# 4-Connector.net
KiCad netlist of a schematic drawn in Altium Designer
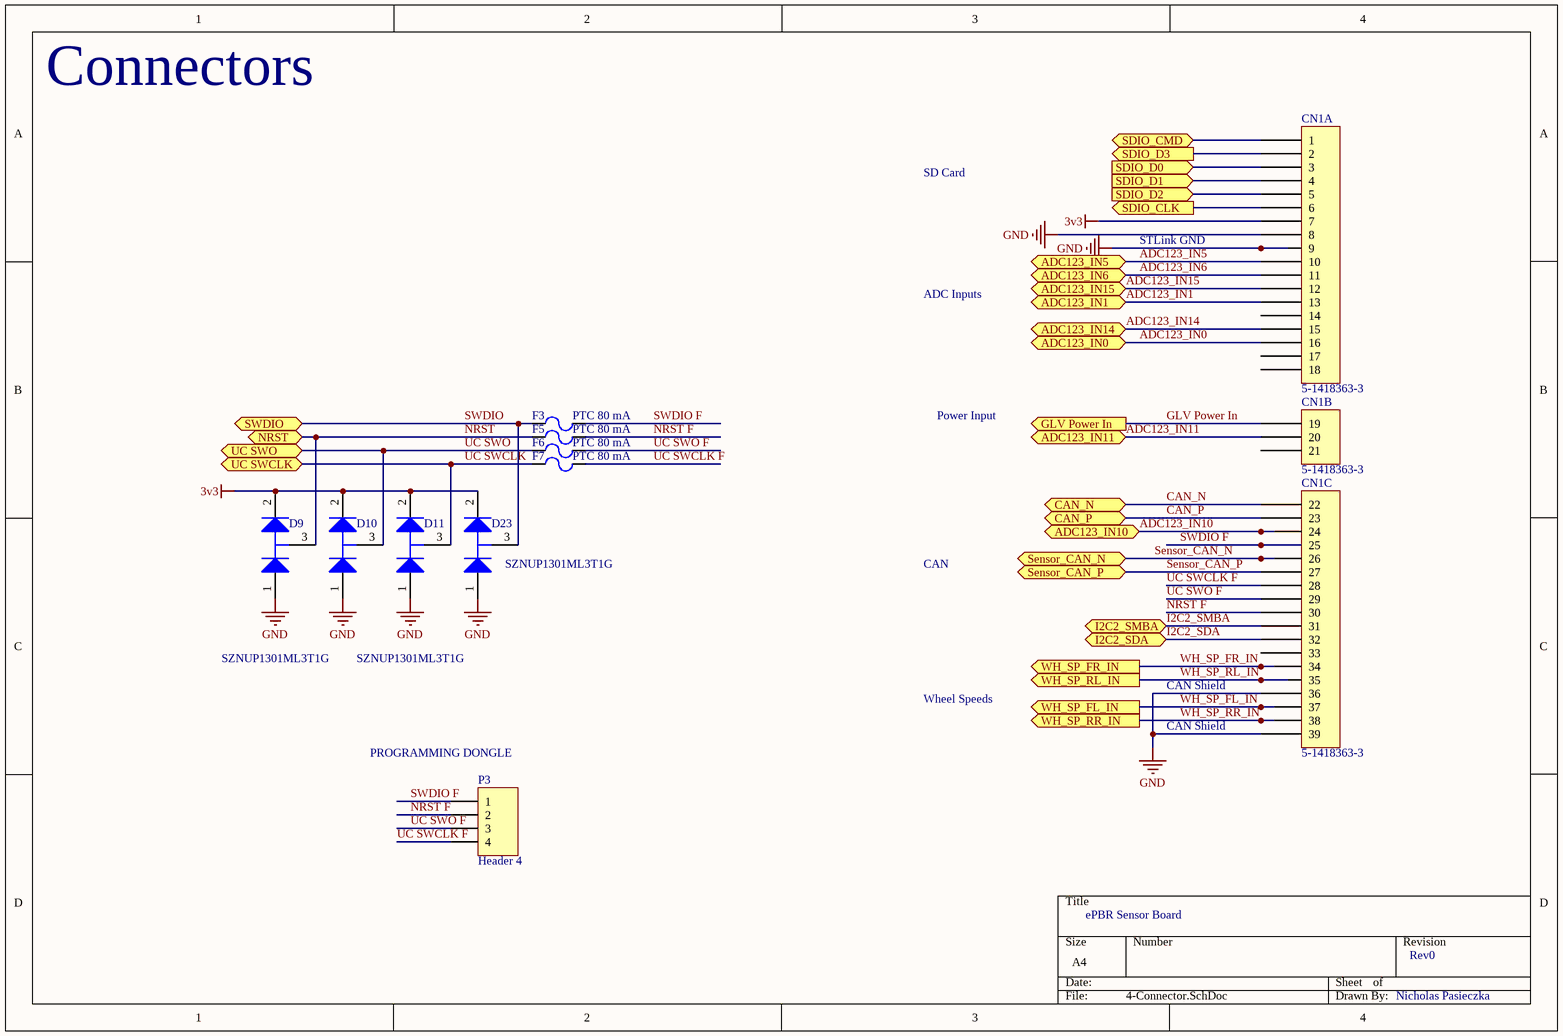
[diagram p0: 4-Connector.SchDoc]

(export (version "E")
  (design (tool "Eeschema 10.0.6"))
  (components
    (comp (ref "CN1")
      (value "5-1418363-3")
      (footprint "5-1418363-3")
      (description "Levyseal 90 degree 39 pin header")
      (libsource (lib "VCB20") (part "5-1418363-3"))
    )
    (comp (ref "D9")
      (value "SZNUP1301ML3T1G")
      (footprint "ONSC-SOT-23-3-318-08_V")
      (fields (field (name "MANUFACTURER") "On Semiconductor"))
      (libsource (lib "Altium Content Vault") (part "ONSC-NUP1301-SOT-23-3-318-08"))
    )
    (comp (ref "D10")
      (value "SZNUP1301ML3T1G")
      (footprint "ONSC-SOT-23-3-318-08_V")
      (fields (field (name "MANUFACTURER") "On Semiconductor"))
      (libsource (lib "Altium Content Vault") (part "ONSC-NUP1301-SOT-23-3-318-08"))
    )
    (comp (ref "D11")
      (value "SZNUP1301ML3T1G")
      (footprint "ONSC-SOT-23-3-318-08_V")
      (fields (field (name "MANUFACTURER") "On Semiconductor"))
      (libsource (lib "Altium Content Vault") (part "ONSC-NUP1301-SOT-23-3-318-08"))
    )
    (comp (ref "D23")
      (value "SZNUP1301ML3T1G")
      (footprint "ONSC-SOT-23-3-318-08_V")
      (fields (field (name "MANUFACTURER") "On Semiconductor"))
      (libsource (lib "Altium Content Vault") (part "ONSC-NUP1301-SOT-23-3-318-08"))
    )
    (comp (ref "F3")
      (value "PTC 80 mA")
      (footprint "0603 fuse")
      (description "0ZCM0008FF2G")
      (libsource (lib "VCU Library") (part "PTC fuse 80mA 0ZCM0008FF2G"))
    )
    (comp (ref "F5")
      (value "PTC 80 mA")
      (footprint "0603 fuse")
      (description "0ZCM0008FF2G")
      (libsource (lib "VCU Library") (part "PTC fuse 80mA 0ZCM0008FF2G"))
    )
    (comp (ref "F6")
      (value "PTC 80 mA")
      (footprint "0603 fuse")
      (description "0ZCM0008FF2G")
      (libsource (lib "VCU Library") (part "PTC fuse 80mA 0ZCM0008FF2G"))
    )
    (comp (ref "F7")
      (value "PTC 80 mA")
      (footprint "0603 fuse")
      (description "0ZCM0008FF2G")
      (libsource (lib "VCU Library") (part "PTC fuse 80mA 0ZCM0008FF2G"))
    )
    (comp (ref "P3")
      (value "Header 4")
      (footprint "HDR1X4")
      (description "Header, 4-Pin")
      (fields (field (name "PUBLISHER") "Altium Limited"))
      (libsource (lib "Miscellaneous Connectors") (part "Header 4"))
    )
  )
  (nets
    (net (code "1") (name "/ADC123_IN0") (class "Default")
      (node (ref "CN1") (pin "16") (pinfunction "16_16") (pintype "passive"))
    )
    (net (code "2") (name "/ADC123_IN1") (class "Default")
      (node (ref "CN1") (pin "13") (pinfunction "13_13") (pintype "passive"))
    )
    (net (code "3") (name "/ADC123_IN5") (class "Default")
      (node (ref "CN1") (pin "10") (pinfunction "10_10") (pintype "passive"))
    )
    (net (code "4") (name "/ADC123_IN6") (class "Default")
      (node (ref "CN1") (pin "11") (pinfunction "11_11") (pintype "passive"))
    )
    (net (code "5") (name "/ADC123_IN10") (class "Default")
      (node (ref "CN1") (pin "24") (pinfunction "24_24") (pintype "passive"))
    )
    (net (code "6") (name "/ADC123_IN11") (class "Default")
      (node (ref "CN1") (pin "20") (pinfunction "20_20") (pintype "passive"))
    )
    (net (code "7") (name "/ADC123_IN14") (class "Default")
      (node (ref "CN1") (pin "15") (pinfunction "15_15") (pintype "passive"))
    )
    (net (code "8") (name "/ADC123_IN15") (class "Default")
      (node (ref "CN1") (pin "12") (pinfunction "12_12") (pintype "passive"))
    )
    (net (code "9") (name "/CAN_N") (class "Default")
      (node (ref "CN1") (pin "22") (pinfunction "22_22") (pintype "passive"))
    )
    (net (code "10") (name "/CAN_P") (class "Default")
      (node (ref "CN1") (pin "23") (pinfunction "23_23") (pintype "passive"))
    )
    (net (code "11") (name "/GLV Power In") (class "Default")
      (node (ref "CN1") (pin "19") (pinfunction "19_19") (pintype "passive"))
    )
    (net (code "12") (name "/I2C2_SDA") (class "Default")
      (node (ref "CN1") (pin "32") (pinfunction "32_32") (pintype "passive"))
    )
    (net (code "13") (name "/I2C2_SMBA") (class "Default")
      (node (ref "CN1") (pin "31") (pinfunction "31_31") (pintype "passive"))
    )
    (net (code "14") (name "/NRST") (class "Default")
      (node (ref "D9") (pin "3") (pinfunction "K/A_3") (pintype "passive"))
      (node (ref "F5") (pin "1") (pinfunction "1_1") (pintype "passive"))
    )
    (net (code "15") (name "/NRST F") (class "Default")
      (node (ref "CN1") (pin "30") (pinfunction "30_30") (pintype "passive"))
      (node (ref "F5") (pin "2") (pinfunction "2_2") (pintype "passive"))
      (node (ref "P3") (pin "2") (pinfunction "2_2") (pintype "passive"))
    )
    (net (code "16") (name "/SDIO_CLK") (class "Default")
      (node (ref "CN1") (pin "6") (pinfunction "6_6") (pintype "passive"))
    )
    (net (code "17") (name "/SDIO_CMD") (class "Default")
      (node (ref "CN1") (pin "1") (pinfunction "1_1") (pintype "passive"))
    )
    (net (code "18") (name "/SDIO_D0") (class "Default")
      (node (ref "CN1") (pin "3") (pinfunction "3_3") (pintype "passive"))
    )
    (net (code "19") (name "/SDIO_D1") (class "Default")
      (node (ref "CN1") (pin "4") (pinfunction "4_4") (pintype "passive"))
    )
    (net (code "20") (name "/SDIO_D2") (class "Default")
      (node (ref "CN1") (pin "5") (pinfunction "5_5") (pintype "passive"))
    )
    (net (code "21") (name "/SDIO_D3") (class "Default")
      (node (ref "CN1") (pin "2") (pinfunction "2_2") (pintype "passive"))
    )
    (net (code "22") (name "/SWDIO") (class "Default")
      (node (ref "D23") (pin "3") (pinfunction "K/A_3") (pintype "passive"))
      (node (ref "F3") (pin "1") (pinfunction "1_1") (pintype "passive"))
    )
    (net (code "23") (name "/SWDIO F") (class "Default")
      (node (ref "CN1") (pin "25") (pinfunction "25_25") (pintype "passive"))
      (node (ref "F3") (pin "2") (pinfunction "2_2") (pintype "passive"))
      (node (ref "P3") (pin "1") (pinfunction "1_1") (pintype "passive"))
    )
    (net (code "24") (name "/Sensor_CAN_N") (class "Default")
      (node (ref "CN1") (pin "26") (pinfunction "26_26") (pintype "passive"))
    )
    (net (code "25") (name "/Sensor_CAN_P") (class "Default")
      (node (ref "CN1") (pin "27") (pinfunction "27_27") (pintype "passive"))
    )
    (net (code "26") (name "/UC SWCLK") (class "Default")
      (node (ref "D11") (pin "3") (pinfunction "K/A_3") (pintype "passive"))
      (node (ref "F7") (pin "1") (pinfunction "1_1") (pintype "passive"))
    )
    (net (code "27") (name "/UC SWCLK F") (class "Default")
      (node (ref "CN1") (pin "28") (pinfunction "28_28") (pintype "passive"))
      (node (ref "F7") (pin "2") (pinfunction "2_2") (pintype "passive"))
      (node (ref "P3") (pin "4") (pinfunction "4_4") (pintype "passive"))
    )
    (net (code "28") (name "/UC SWO") (class "Default")
      (node (ref "D10") (pin "3") (pinfunction "K/A_3") (pintype "passive"))
      (node (ref "F6") (pin "1") (pinfunction "1_1") (pintype "passive"))
    )
    (net (code "29") (name "/UC SWO F") (class "Default")
      (node (ref "CN1") (pin "29") (pinfunction "29_29") (pintype "passive"))
      (node (ref "F6") (pin "2") (pinfunction "2_2") (pintype "passive"))
      (node (ref "P3") (pin "3") (pinfunction "3_3") (pintype "passive"))
    )
    (net (code "30") (name "/WH_SP_FL_IN") (class "Default")
      (node (ref "CN1") (pin "37") (pinfunction "37_37") (pintype "passive"))
    )
    (net (code "31") (name "/WH_SP_FR_IN") (class "Default")
      (node (ref "CN1") (pin "34") (pinfunction "34_34") (pintype "passive"))
    )
    (net (code "32") (name "/WH_SP_RL_IN") (class "Default")
      (node (ref "CN1") (pin "35") (pinfunction "35_35") (pintype "passive"))
    )
    (net (code "33") (name "/WH_SP_RR_IN") (class "Default")
      (node (ref "CN1") (pin "38") (pinfunction "38_38") (pintype "passive"))
    )
    (net (code "34") (name "3v3") (class "Default")
      (node (ref "CN1") (pin "7") (pinfunction "7_7") (pintype "passive"))
      (node (ref "D10") (pin "2") (pinfunction "K_2") (pintype "passive"))
      (node (ref "D11") (pin "2") (pinfunction "K_2") (pintype "passive"))
      (node (ref "D23") (pin "2") (pinfunction "K_2") (pintype "passive"))
      (node (ref "D9") (pin "2") (pinfunction "K_2") (pintype "passive"))
    )
    (net (code "35") (name "GND") (class "Default")
      (node (ref "CN1") (pin "36") (pinfunction "36_36") (pintype "passive"))
      (node (ref "CN1") (pin "39") (pinfunction "39_39") (pintype "passive"))
      (node (ref "CN1") (pin "8") (pinfunction "8_8") (pintype "passive"))
      (node (ref "CN1") (pin "9") (pinfunction "9_9") (pintype "passive"))
      (node (ref "D10") (pin "1") (pinfunction "A_1") (pintype "passive"))
      (node (ref "D11") (pin "1") (pinfunction "A_1") (pintype "passive"))
      (node (ref "D23") (pin "1") (pinfunction "A_1") (pintype "passive"))
      (node (ref "D9") (pin "1") (pinfunction "A_1") (pintype "passive"))
    )
    (net (code "36") (name "unconnected-(CN1-Pad14)") (class "Default")
      (node (ref "CN1") (pin "14") (pinfunction "14_14") (pintype "passive"))
    )
    (net (code "37") (name "unconnected-(CN1-Pad17)") (class "Default")
      (node (ref "CN1") (pin "17") (pinfunction "17_17") (pintype "passive"))
    )
    (net (code "38") (name "unconnected-(CN1-Pad18)") (class "Default")
      (node (ref "CN1") (pin "18") (pinfunction "18_18") (pintype "passive"))
    )
    (net (code "39") (name "unconnected-(CN1-Pad21)") (class "Default")
      (node (ref "CN1") (pin "21") (pinfunction "21_21") (pintype "passive"))
    )
    (net (code "40") (name "unconnected-(CN1-Pad33)") (class "Default")
      (node (ref "CN1") (pin "33") (pinfunction "33_33") (pintype "passive"))
    )
  )
)
